# Enclosure_110x110_SWT.net
KiCad netlist of a schematic drawn in EAGLE
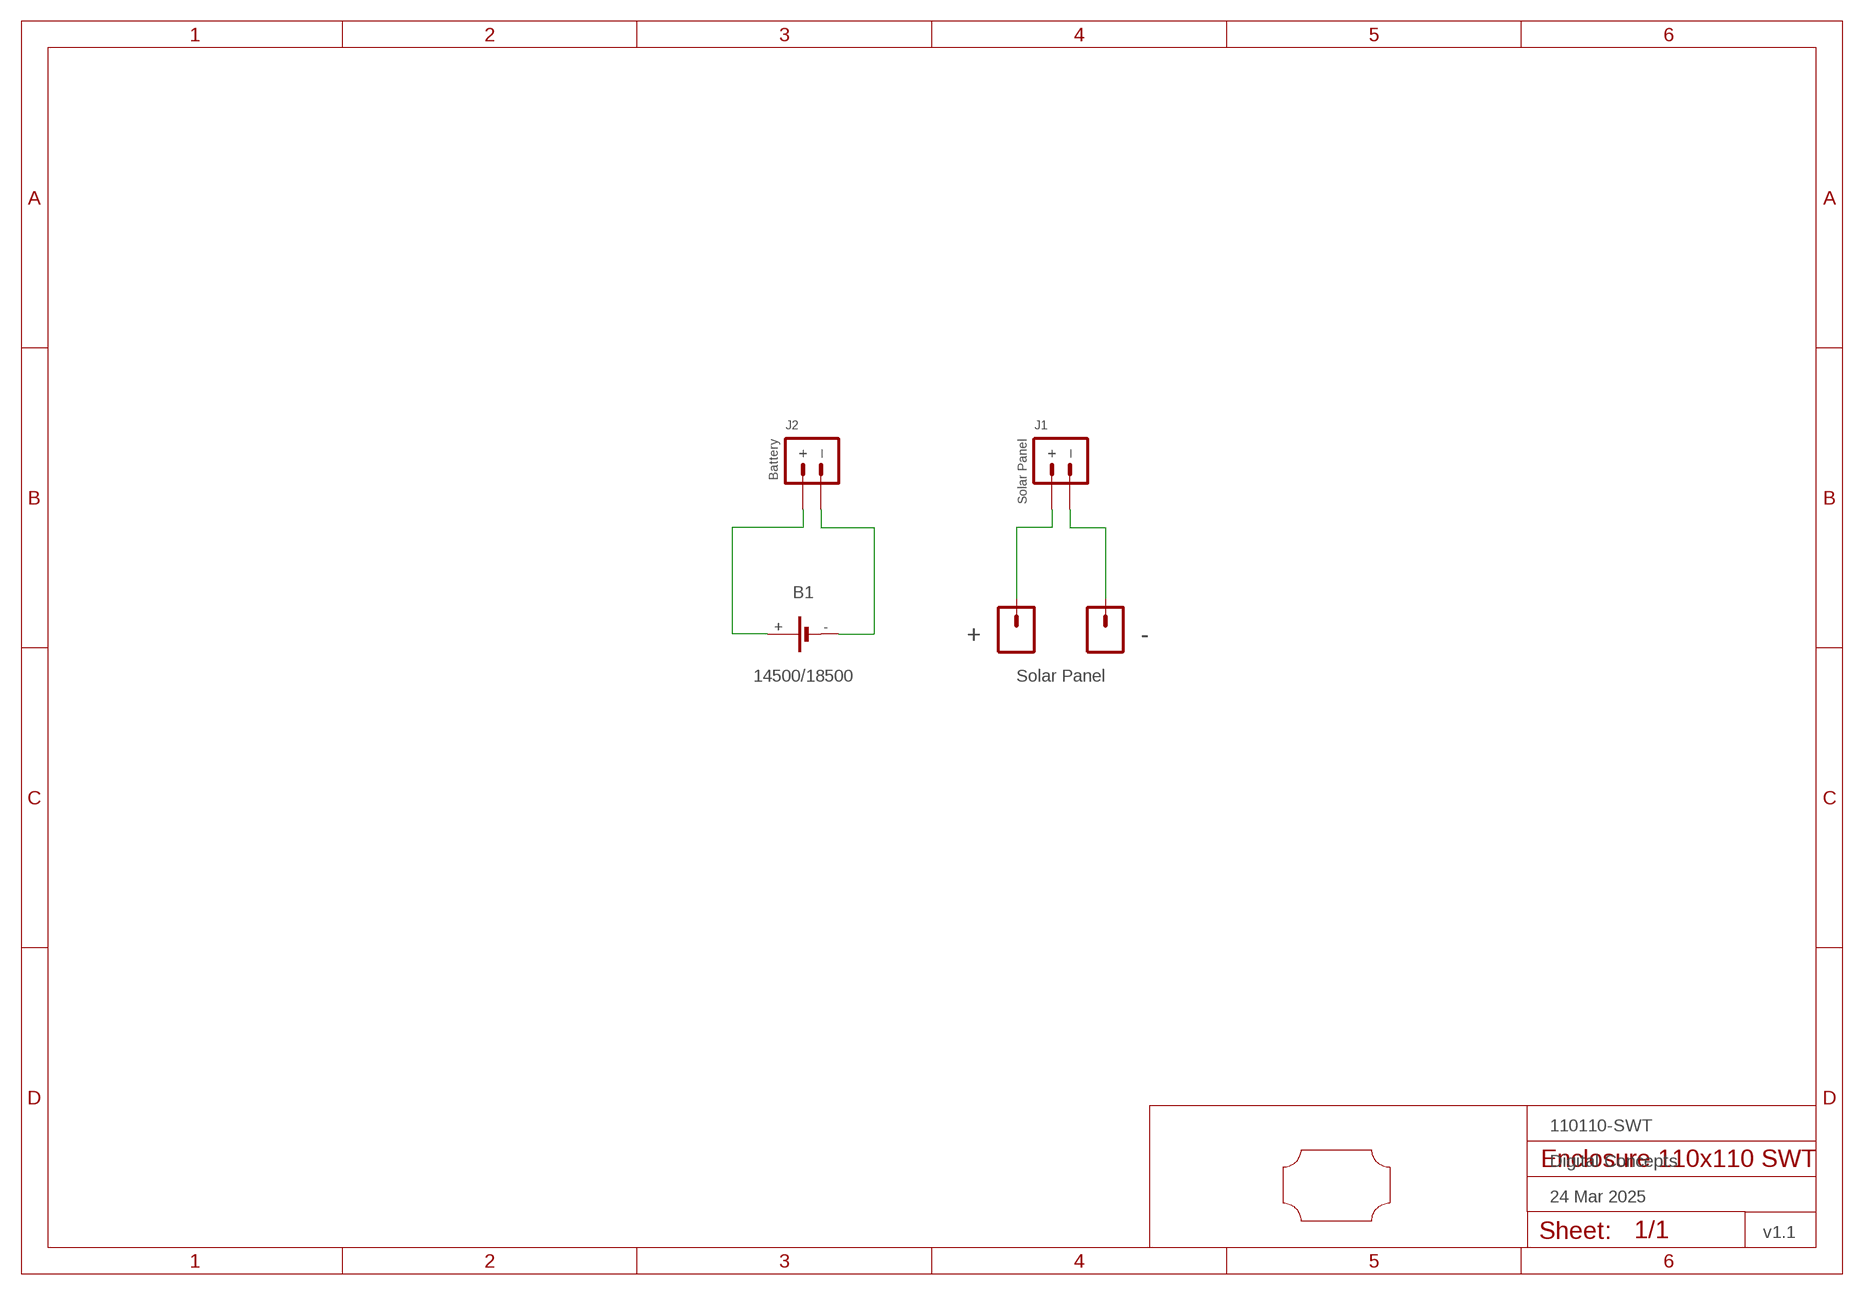
[diagram p0: schematic, sheet 1]

(export (version "E")
  (design (tool "Eeschema 10.0.6"))
  (components
    (comp (ref "+")
      (value "PAD-SMD-GENERIC-SQUARE")
      (footprint "eagle-import:PAD-SMD-GENERIC")
      (libsource (lib "eagle-import") (part "PAD-SMD-GENERIC-SQUARE"))
    )
    (comp (ref "-")
      (value "PAD-SMD-GENERIC-SQUARE")
      (footprint "eagle-import:PAD-SMD-GENERIC")
      (libsource (lib "eagle-import") (part "PAD-SMD-GENERIC-SQUARE"))
    )
    (comp (ref "B1")
      (value "14500/18500")
      (footprint "eagle-import:BATTERY-14500_18500")
      (libsource (lib "eagle-import") (part "BATTERY-HOLDER-14500/18500"))
    )
    (comp (ref "J1")
      (value "Solar Panel")
      (footprint "eagle-import:JST-PH2.0-2-HORIZONTAL-POWER")
      (libsource (lib "eagle-import") (part "JST-PH2.0-2-HORIZONTAL-POWERJST-PTH-2"))
    )
    (comp (ref "J2")
      (value "Battery")
      (footprint "eagle-import:JST-PH2.0-2-HORIZONTAL-POWER")
      (libsource (lib "eagle-import") (part "JST-PH2.0-2-HORIZONTAL-POWERJST-PTH-2"))
    )
    (comp (ref "U$1")
      (value "PCB-OUTLINE-110X110")
      (footprint "eagle-import:PROTO-110X110-OUTLINE")
      (libsource (lib "eagle-import") (part "PCB-OUTLINE-110X110"))
    )
  )
  (nets
    (net (code "1") (name "Net-(+-1)") (class "Default")
      (node (ref "+") (pin "P$1") (pinfunction "1_P$1") (pintype "passive"))
      (node (ref "J1") (pin "+") (pinfunction "+_+") (pintype "power_in"))
    )
    (net (code "2") (name "Net-(--1)") (class "Default")
      (node (ref "-") (pin "P$1") (pinfunction "1_P$1") (pintype "passive"))
      (node (ref "J1") (pin "-") (pinfunction "–_-") (pintype "power_in"))
    )
    (net (code "3") (name "Net-(B1-Pad+)") (class "Default")
      (node (ref "B1") (pin "+") (pinfunction "+_+") (pintype "power_in"))
      (node (ref "J2") (pin "+") (pinfunction "+_+") (pintype "power_in"))
    )
    (net (code "4") (name "Net-(J2-–)") (class "Default")
      (node (ref "B1") (pin "-") (pinfunction "-_-") (pintype "power_in"))
      (node (ref "J2") (pin "-") (pinfunction "–_-") (pintype "power_in"))
    )
  )
)
